# Hat_CoVASPSy_v1re2.net
KiCad netlist of a schematic drawn in EAGLE
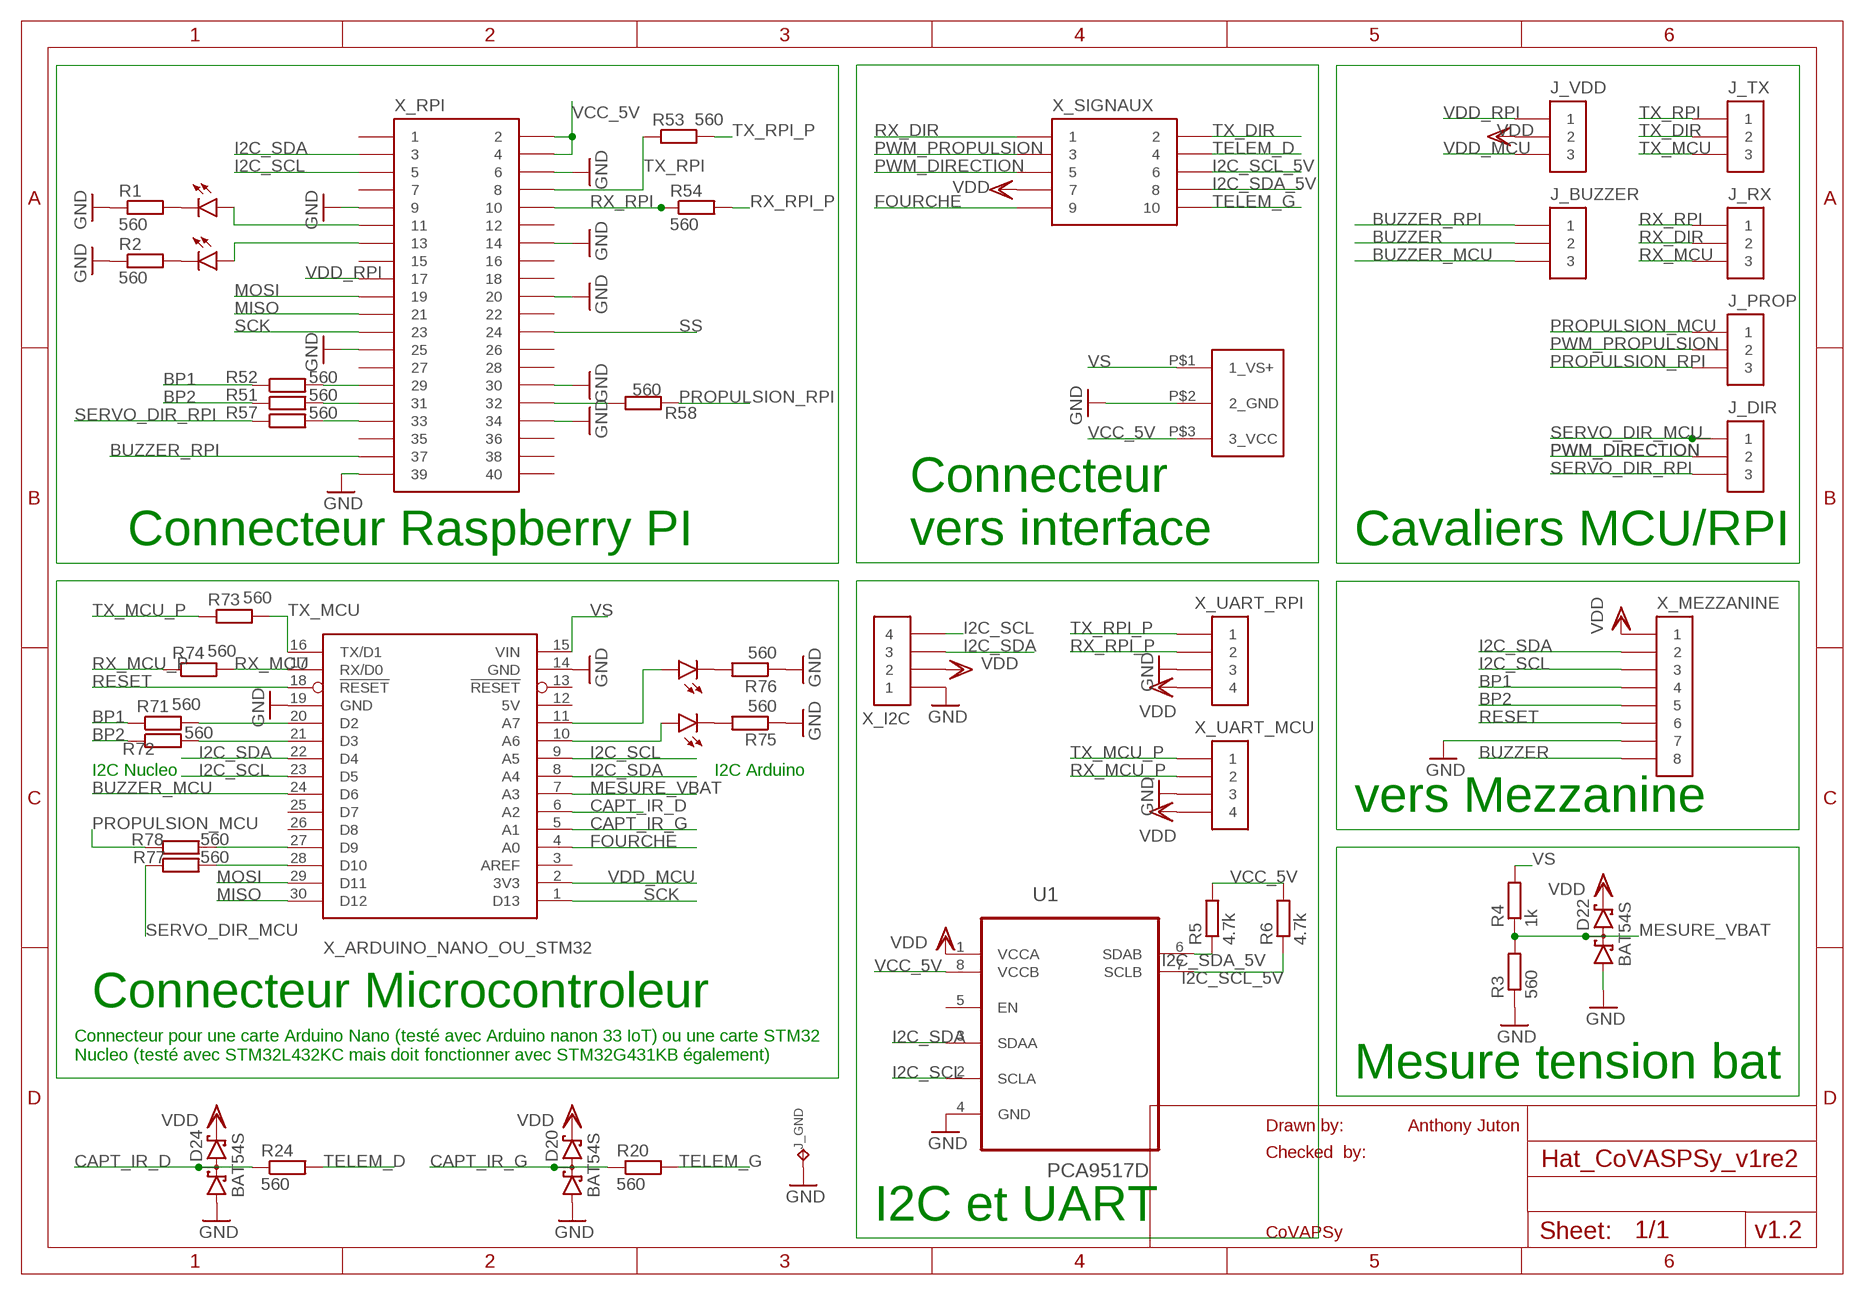
[diagram p0: schematic, sheet 1]

(export (version "E")
  (design (tool "Eeschema 10.0.6"))
  (components
    (comp (ref "D20")
      (value "BAT54S")
      (footprint "eagle-import:SOT23")
      (libsource (lib "eagle-import") (part "BAT54S"))
    )
    (comp (ref "D22")
      (value "BAT54S")
      (footprint "eagle-import:SOT23")
      (libsource (lib "eagle-import") (part "BAT54S"))
    )
    (comp (ref "D24")
      (value "BAT54S")
      (footprint "eagle-import:SOT23")
      (libsource (lib "eagle-import") (part "BAT54S"))
    )
    (comp (ref "J_BUZZER")
      (value "CAVALIER_3")
      (footprint "eagle-import:CAVALIER_3")
      (libsource (lib "eagle-import") (part "CAVALIER_3"))
    )
    (comp (ref "J_DIR")
      (value "CAVALIER_3")
      (footprint "eagle-import:CAVALIER_3")
      (libsource (lib "eagle-import") (part "CAVALIER_3"))
    )
    (comp (ref "J_GND")
      (value "COSSE_POIGN")
      (footprint "eagle-import:COSSE_POIGNARD")
      (libsource (lib "eagle-import") (part "COSSE_POIGN"))
    )
    (comp (ref "J_PROP")
      (value "CAVALIER_3")
      (footprint "eagle-import:CAVALIER_3")
      (libsource (lib "eagle-import") (part "CAVALIER_3"))
    )
    (comp (ref "J_RX")
      (value "CAVALIER_3")
      (footprint "eagle-import:CAVALIER_3")
      (libsource (lib "eagle-import") (part "CAVALIER_3"))
    )
    (comp (ref "J_TX")
      (value "CAVALIER_3")
      (footprint "eagle-import:CAVALIER_3")
      (libsource (lib "eagle-import") (part "CAVALIER_3"))
    )
    (comp (ref "J_VDD")
      (value "CAVALIER_3")
      (footprint "eagle-import:CAVALIER_3")
      (libsource (lib "eagle-import") (part "CAVALIER_3"))
    )
    (comp (ref "LED1")
      (value "LEDSML1206")
      (footprint "eagle-import:SML1206")
      (libsource (lib "eagle-import") (part "LEDSML1206"))
    )
    (comp (ref "LED2")
      (value "LEDSML1206")
      (footprint "eagle-import:SML1206")
      (libsource (lib "eagle-import") (part "LEDSML1206"))
    )
    (comp (ref "LED3")
      (value "LEDSML1206")
      (footprint "eagle-import:SML1206")
      (libsource (lib "eagle-import") (part "LEDSML1206"))
    )
    (comp (ref "LED4")
      (value "LEDSML1206")
      (footprint "eagle-import:SML1206")
      (libsource (lib "eagle-import") (part "LEDSML1206"))
    )
    (comp (ref "R1")
      (value "560")
      (footprint "eagle-import:M1206")
      (libsource (lib "eagle-import") (part "R-EU_M1206"))
    )
    (comp (ref "R2")
      (value "560")
      (footprint "eagle-import:M1206")
      (libsource (lib "eagle-import") (part "R-EU_M1206"))
    )
    (comp (ref "R3")
      (value "560")
      (footprint "eagle-import:M1206")
      (libsource (lib "eagle-import") (part "R-EU_M1206"))
    )
    (comp (ref "R4")
      (value "1k")
      (footprint "eagle-import:M1206")
      (libsource (lib "eagle-import") (part "R-EU_M1206"))
    )
    (comp (ref "R5")
      (value "4.7k")
      (footprint "eagle-import:M1206")
      (libsource (lib "eagle-import") (part "R-EU_M1206"))
    )
    (comp (ref "R6")
      (value "4.7k")
      (footprint "eagle-import:M1206")
      (libsource (lib "eagle-import") (part "R-EU_M1206"))
    )
    (comp (ref "R20")
      (value "560")
      (footprint "eagle-import:M1206")
      (libsource (lib "eagle-import") (part "R-EU_M1206"))
    )
    (comp (ref "R24")
      (value "560")
      (footprint "eagle-import:M1206")
      (libsource (lib "eagle-import") (part "R-EU_M1206"))
    )
    (comp (ref "R51")
      (value "560")
      (footprint "eagle-import:M1206")
      (libsource (lib "eagle-import") (part "R-EU_M1206"))
    )
    (comp (ref "R52")
      (value "560")
      (footprint "eagle-import:M1206")
      (libsource (lib "eagle-import") (part "R-EU_M1206"))
    )
    (comp (ref "R53")
      (value "560")
      (footprint "eagle-import:M1206")
      (libsource (lib "eagle-import") (part "R-EU_M1206"))
    )
    (comp (ref "R54")
      (value "560")
      (footprint "eagle-import:M1206")
      (libsource (lib "eagle-import") (part "R-EU_M1206"))
    )
    (comp (ref "R57")
      (value "560")
      (footprint "eagle-import:M1206")
      (libsource (lib "eagle-import") (part "R-EU_M1206"))
    )
    (comp (ref "R58")
      (value "560")
      (footprint "eagle-import:M1206")
      (libsource (lib "eagle-import") (part "R-EU_M1206"))
    )
    (comp (ref "R71")
      (value "560")
      (footprint "eagle-import:M1206")
      (libsource (lib "eagle-import") (part "R-EU_M1206"))
    )
    (comp (ref "R72")
      (value "560")
      (footprint "eagle-import:M1206")
      (libsource (lib "eagle-import") (part "R-EU_M1206"))
    )
    (comp (ref "R73")
      (value "560")
      (footprint "eagle-import:M1206")
      (libsource (lib "eagle-import") (part "R-EU_M1206"))
    )
    (comp (ref "R74")
      (value "560")
      (footprint "eagle-import:M1206")
      (libsource (lib "eagle-import") (part "R-EU_M1206"))
    )
    (comp (ref "R75")
      (value "560")
      (footprint "eagle-import:M1206")
      (libsource (lib "eagle-import") (part "R-EU_M1206"))
    )
    (comp (ref "R76")
      (value "560")
      (footprint "eagle-import:M1206")
      (libsource (lib "eagle-import") (part "R-EU_M1206"))
    )
    (comp (ref "R77")
      (value "560")
      (footprint "eagle-import:M1206")
      (libsource (lib "eagle-import") (part "R-EU_M1206"))
    )
    (comp (ref "R78")
      (value "560")
      (footprint "eagle-import:M1206")
      (libsource (lib "eagle-import") (part "R-EU_M1206"))
    )
    (comp (ref "U1")
      (value "PCA9517D")
      (footprint "eagle-import:SOIC127P600X175-8N")
      (libsource (lib "eagle-import") (part "PCA9517D"))
    )
    (comp (ref "X_ALIM")
      (value "CONN_ALIM_3TROUS")
      (footprint "eagle-import:CONN_ALIM_3TROUS")
      (libsource (lib "eagle-import") (part "CONN_ALIM_3TROUS"))
    )
    (comp (ref "X_ARDUINO_NANO_OU_STM32")
      (value "ARDUINO_NANO_STM32_NUCLEO")
      (footprint "eagle-import:ARDUINO_NANO_STM32_NUCLEO")
      (libsource (lib "eagle-import") (part "ARDUINO_NANO_STM32_NUCLEO"))
    )
    (comp (ref "X_I2C")
      (value "MOLEX_4_DROIT")
      (footprint "eagle-import:MOLEX_4_DROIT")
      (libsource (lib "eagle-import") (part "MOLEX_4_DROIT"))
    )
    (comp (ref "X_MEZZANINE")
      (value "MOLEX_8_DROIT")
      (footprint "eagle-import:MOLEX_8_DROIT")
      (libsource (lib "eagle-import") (part "MOLEX_8_DROIT"))
    )
    (comp (ref "X_RPI")
      (value "HEADER_20X2")
      (footprint "eagle-import:HEADER_20X2")
      (libsource (lib "eagle-import") (part "HEADER_20X2"))
    )
    (comp (ref "X_SIGNAUX")
      (value "HEADER_5X2")
      (footprint "eagle-import:HEADER_5X2")
      (libsource (lib "eagle-import") (part "HEADER_5X2"))
    )
    (comp (ref "X_UART_MCU")
      (value "MOLEX_4_DROIT")
      (footprint "eagle-import:MOLEX_4_DROIT")
      (libsource (lib "eagle-import") (part "MOLEX_4_DROIT"))
    )
    (comp (ref "X_UART_RPI")
      (value "MOLEX_4_DROIT")
      (footprint "eagle-import:MOLEX_4_DROIT")
      (libsource (lib "eagle-import") (part "MOLEX_4_DROIT"))
    )
  )
  (nets
    (net (code "1") (name "/5V") (class "Default")
      (node (ref "X_ARDUINO_NANO_OU_STM32") (pin "12") (pinfunction "5V_12") (pintype "power_in"))
    )
    (net (code "2") (name "/BP1") (class "Default")
      (node (ref "R52") (pin "1") (pinfunction "1_1") (pintype "passive"))
      (node (ref "R71") (pin "1") (pinfunction "1_1") (pintype "passive"))
      (node (ref "X_MEZZANINE") (pin "P$4") (pinfunction "4_P$4") (pintype "bidirectional"))
    )
    (net (code "3") (name "/BP2") (class "Default")
      (node (ref "R51") (pin "1") (pinfunction "1_1") (pintype "passive"))
      (node (ref "R72") (pin "1") (pinfunction "1_1") (pintype "passive"))
      (node (ref "X_MEZZANINE") (pin "P$5") (pinfunction "5_P$5") (pintype "bidirectional"))
    )
    (net (code "4") (name "/BUZZER") (class "Default")
      (node (ref "J_BUZZER") (pin "P$2") (pinfunction "2_P$2") (pintype "bidirectional"))
      (node (ref "X_MEZZANINE") (pin "P$8") (pinfunction "8_P$8") (pintype "bidirectional"))
    )
    (net (code "5") (name "/BUZZER_MCU") (class "Default")
      (node (ref "J_BUZZER") (pin "P$3") (pinfunction "3_P$3") (pintype "bidirectional"))
      (node (ref "X_ARDUINO_NANO_OU_STM32") (pin "24") (pinfunction "D6_24") (pintype "bidirectional"))
    )
    (net (code "6") (name "/BUZZER_RPI") (class "Default")
      (node (ref "J_BUZZER") (pin "P$1") (pinfunction "1_P$1") (pintype "bidirectional"))
      (node (ref "X_RPI") (pin "P$37") (pinfunction "37_P$37") (pintype "bidirectional"))
    )
    (net (code "7") (name "/CAPT_IR_D") (class "Default")
      (node (ref "D24") (pin "3") (pinfunction "C1A2_3") (pintype "passive"))
      (node (ref "R24") (pin "1") (pinfunction "1_1") (pintype "passive"))
      (node (ref "X_ARDUINO_NANO_OU_STM32") (pin "6") (pinfunction "A2_6") (pintype "bidirectional"))
    )
    (net (code "8") (name "/CAPT_IR_G") (class "Default")
      (node (ref "D20") (pin "3") (pinfunction "C1A2_3") (pintype "passive"))
      (node (ref "R20") (pin "1") (pinfunction "1_1") (pintype "passive"))
      (node (ref "X_ARDUINO_NANO_OU_STM32") (pin "5") (pinfunction "A1_5") (pintype "bidirectional"))
    )
    (net (code "9") (name "/FOURCHE") (class "Default")
      (node (ref "X_ARDUINO_NANO_OU_STM32") (pin "4") (pinfunction "A0_4") (pintype "bidirectional"))
      (node (ref "X_SIGNAUX") (pin "P$9") (pinfunction "9_P$9") (pintype "bidirectional"))
    )
    (net (code "10") (name "/I2C_SCL") (class "Default")
      (node (ref "U1") (pin "2") (pinfunction "SCLA_2") (pintype "input"))
      (node (ref "X_ARDUINO_NANO_OU_STM32") (pin "23") (pinfunction "D5_23") (pintype "bidirectional"))
      (node (ref "X_ARDUINO_NANO_OU_STM32") (pin "9") (pinfunction "A5_9") (pintype "bidirectional"))
      (node (ref "X_I2C") (pin "P$4") (pinfunction "4_P$4") (pintype "bidirectional"))
      (node (ref "X_MEZZANINE") (pin "P$3") (pinfunction "3_P$3") (pintype "bidirectional"))
      (node (ref "X_RPI") (pin "P$5") (pinfunction "5_P$5") (pintype "bidirectional"))
    )
    (net (code "11") (name "/I2C_SCL_5V") (class "Default")
      (node (ref "R6") (pin "1") (pinfunction "1_1") (pintype "passive"))
      (node (ref "U1") (pin "7") (pinfunction "SCLB_7") (pintype "output"))
      (node (ref "X_SIGNAUX") (pin "P$6") (pinfunction "6_P$6") (pintype "bidirectional"))
    )
    (net (code "12") (name "/I2C_SDA") (class "Default")
      (node (ref "U1") (pin "3") (pinfunction "SDAA_3") (pintype "input"))
      (node (ref "X_ARDUINO_NANO_OU_STM32") (pin "22") (pinfunction "D4_22") (pintype "bidirectional"))
      (node (ref "X_ARDUINO_NANO_OU_STM32") (pin "8") (pinfunction "A4_8") (pintype "bidirectional"))
      (node (ref "X_I2C") (pin "P$3") (pinfunction "3_P$3") (pintype "bidirectional"))
      (node (ref "X_MEZZANINE") (pin "P$2") (pinfunction "2_P$2") (pintype "bidirectional"))
      (node (ref "X_RPI") (pin "P$3") (pinfunction "3_P$3") (pintype "bidirectional"))
    )
    (net (code "13") (name "/I2C_SDA_5V") (class "Default")
      (node (ref "R5") (pin "1") (pinfunction "1_1") (pintype "passive"))
      (node (ref "U1") (pin "6") (pinfunction "SDAB_6") (pintype "output"))
      (node (ref "X_SIGNAUX") (pin "P$8") (pinfunction "8_P$8") (pintype "bidirectional"))
    )
    (net (code "14") (name "/MESURE_VBAT") (class "Default")
      (node (ref "D22") (pin "3") (pinfunction "C1A2_3") (pintype "passive"))
      (node (ref "R3") (pin "2") (pinfunction "2_2") (pintype "passive"))
      (node (ref "R4") (pin "1") (pinfunction "1_1") (pintype "passive"))
      (node (ref "X_ARDUINO_NANO_OU_STM32") (pin "7") (pinfunction "A3_7") (pintype "bidirectional"))
    )
    (net (code "15") (name "/MISO") (class "Default")
      (node (ref "X_ARDUINO_NANO_OU_STM32") (pin "30") (pinfunction "D12_30") (pintype "bidirectional"))
      (node (ref "X_RPI") (pin "P$21") (pinfunction "21_P$21") (pintype "bidirectional"))
    )
    (net (code "16") (name "/MOSI") (class "Default")
      (node (ref "X_ARDUINO_NANO_OU_STM32") (pin "29") (pinfunction "D11_29") (pintype "bidirectional"))
      (node (ref "X_RPI") (pin "P$19") (pinfunction "19_P$19") (pintype "bidirectional"))
    )
    (net (code "20") (name "/PROPULSION_MCU") (class "Default")
      (node (ref "J_PROP") (pin "P$1") (pinfunction "1_P$1") (pintype "bidirectional"))
      (node (ref "R78") (pin "1") (pinfunction "1_1") (pintype "passive"))
    )
    (net (code "21") (name "/PROPULSION_RPI") (class "Default")
      (node (ref "J_PROP") (pin "P$3") (pinfunction "3_P$3") (pintype "bidirectional"))
      (node (ref "R58") (pin "2") (pinfunction "2_2") (pintype "passive"))
    )
    (net (code "22") (name "/PWM_DIRECTION") (class "Default")
      (node (ref "J_DIR") (pin "P$2") (pinfunction "2_P$2") (pintype "bidirectional"))
      (node (ref "X_SIGNAUX") (pin "P$5") (pinfunction "5_P$5") (pintype "bidirectional"))
    )
    (net (code "23") (name "/PWM_PROPULSION") (class "Default")
      (node (ref "J_PROP") (pin "P$2") (pinfunction "2_P$2") (pintype "bidirectional"))
      (node (ref "X_SIGNAUX") (pin "P$3") (pinfunction "3_P$3") (pintype "bidirectional"))
    )
    (net (code "24") (name "/RESET") (class "Default")
      (node (ref "X_ARDUINO_NANO_OU_STM32") (pin "18") (pinfunction "~{RESET}_18") (pintype "input"))
      (node (ref "X_MEZZANINE") (pin "P$6") (pinfunction "6_P$6") (pintype "bidirectional"))
    )
    (net (code "25") (name "/RX_DIR") (class "Default")
      (node (ref "J_RX") (pin "P$2") (pinfunction "2_P$2") (pintype "bidirectional"))
      (node (ref "X_SIGNAUX") (pin "P$1") (pinfunction "1_P$1") (pintype "bidirectional"))
    )
    (net (code "26") (name "/RX_MCU") (class "Default")
      (node (ref "J_RX") (pin "P$3") (pinfunction "3_P$3") (pintype "bidirectional"))
      (node (ref "R74") (pin "2") (pinfunction "2_2") (pintype "passive"))
      (node (ref "X_ARDUINO_NANO_OU_STM32") (pin "17") (pinfunction "RX/D0_17") (pintype "bidirectional"))
    )
    (net (code "27") (name "/RX_MCU_P") (class "Default")
      (node (ref "R74") (pin "1") (pinfunction "1_1") (pintype "passive"))
      (node (ref "X_UART_MCU") (pin "P$2") (pinfunction "2_P$2") (pintype "bidirectional"))
    )
    (net (code "28") (name "/RX_RPI") (class "Default")
      (node (ref "J_RX") (pin "P$1") (pinfunction "1_P$1") (pintype "bidirectional"))
      (node (ref "R54") (pin "1") (pinfunction "1_1") (pintype "passive"))
      (node (ref "X_RPI") (pin "P$10") (pinfunction "10_P$10") (pintype "bidirectional"))
    )
    (net (code "29") (name "/RX_RPI_P") (class "Default")
      (node (ref "R54") (pin "2") (pinfunction "2_2") (pintype "passive"))
      (node (ref "X_UART_RPI") (pin "P$2") (pinfunction "2_P$2") (pintype "bidirectional"))
    )
    (net (code "30") (name "/SCK") (class "Default")
      (node (ref "X_ARDUINO_NANO_OU_STM32") (pin "1") (pinfunction "D13_1") (pintype "bidirectional"))
      (node (ref "X_RPI") (pin "P$23") (pinfunction "23_P$23") (pintype "bidirectional"))
    )
    (net (code "31") (name "/SERVO_DIR_MCU") (class "Default")
      (node (ref "J_DIR") (pin "P$1") (pinfunction "1_P$1") (pintype "bidirectional"))
      (node (ref "R77") (pin "1") (pinfunction "1_1") (pintype "passive"))
    )
    (net (code "32") (name "/SERVO_DIR_RPI") (class "Default")
      (node (ref "J_DIR") (pin "P$3") (pinfunction "3_P$3") (pintype "bidirectional"))
      (node (ref "R57") (pin "1") (pinfunction "1_1") (pintype "passive"))
    )
    (net (code "33") (name "/SS") (class "Default")
      (node (ref "X_RPI") (pin "P$24") (pinfunction "24_P$24") (pintype "bidirectional"))
    )
    (net (code "34") (name "/TELEM_D") (class "Default")
      (node (ref "R24") (pin "2") (pinfunction "2_2") (pintype "passive"))
      (node (ref "X_SIGNAUX") (pin "P$4") (pinfunction "4_P$4") (pintype "bidirectional"))
    )
    (net (code "35") (name "/TELEM_G") (class "Default")
      (node (ref "R20") (pin "2") (pinfunction "2_2") (pintype "passive"))
      (node (ref "X_SIGNAUX") (pin "P$10") (pinfunction "10_P$10") (pintype "bidirectional"))
    )
    (net (code "36") (name "/TX_DIR") (class "Default")
      (node (ref "J_TX") (pin "P$2") (pinfunction "2_P$2") (pintype "bidirectional"))
      (node (ref "X_SIGNAUX") (pin "P$2") (pinfunction "2_P$2") (pintype "bidirectional"))
    )
    (net (code "37") (name "/TX_MCU") (class "Default")
      (node (ref "J_TX") (pin "P$3") (pinfunction "3_P$3") (pintype "bidirectional"))
      (node (ref "R73") (pin "2") (pinfunction "2_2") (pintype "passive"))
      (node (ref "X_ARDUINO_NANO_OU_STM32") (pin "16") (pinfunction "TX/D1_16") (pintype "bidirectional"))
    )
    (net (code "38") (name "/TX_MCU_P") (class "Default")
      (node (ref "R73") (pin "1") (pinfunction "1_1") (pintype "passive"))
      (node (ref "X_UART_MCU") (pin "P$1") (pinfunction "1_P$1") (pintype "bidirectional"))
    )
    (net (code "39") (name "/TX_RPI") (class "Default")
      (node (ref "J_TX") (pin "P$1") (pinfunction "1_P$1") (pintype "bidirectional"))
      (node (ref "R53") (pin "1") (pinfunction "1_1") (pintype "passive"))
      (node (ref "X_RPI") (pin "P$8") (pinfunction "8_P$8") (pintype "bidirectional"))
    )
    (net (code "40") (name "/TX_RPI_P") (class "Default")
      (node (ref "R53") (pin "2") (pinfunction "2_2") (pintype "passive"))
      (node (ref "X_UART_RPI") (pin "P$1") (pinfunction "1_P$1") (pintype "bidirectional"))
    )
    (net (code "41") (name "/VCC_5V") (class "Default")
      (node (ref "R5") (pin "2") (pinfunction "2_2") (pintype "passive"))
      (node (ref "R6") (pin "2") (pinfunction "2_2") (pintype "passive"))
      (node (ref "U1") (pin "8") (pinfunction "VCCB_8") (pintype "power_in"))
      (node (ref "X_ALIM") (pin "P$3") (pinfunction "3_VCC_P$3") (pintype "bidirectional"))
      (node (ref "X_RPI") (pin "P$2") (pinfunction "2_P$2") (pintype "bidirectional"))
      (node (ref "X_RPI") (pin "P$4") (pinfunction "4_P$4") (pintype "bidirectional"))
    )
    (net (code "42") (name "/VDD_MCU") (class "Default")
      (node (ref "J_VDD") (pin "P$3") (pinfunction "3_P$3") (pintype "bidirectional"))
      (node (ref "X_ARDUINO_NANO_OU_STM32") (pin "2") (pinfunction "3V3_2") (pintype "output"))
    )
    (net (code "43") (name "/VDD_RPI") (class "Default")
      (node (ref "J_VDD") (pin "P$1") (pinfunction "1_P$1") (pintype "bidirectional"))
      (node (ref "X_RPI") (pin "P$17") (pinfunction "17_P$17") (pintype "bidirectional"))
    )
    (net (code "44") (name "/VS") (class "Default")
      (node (ref "R4") (pin "2") (pinfunction "2_2") (pintype "passive"))
      (node (ref "X_ALIM") (pin "P$1") (pinfunction "1_VS+_P$1") (pintype "bidirectional"))
      (node (ref "X_ARDUINO_NANO_OU_STM32") (pin "15") (pinfunction "VIN_15") (pintype "power_in"))
    )
    (net (code "45") (name "GND") (class "Default")
      (node (ref "D20") (pin "1") (pinfunction "A1_1") (pintype "passive"))
      (node (ref "D22") (pin "1") (pinfunction "A1_1") (pintype "passive"))
      (node (ref "D24") (pin "1") (pinfunction "A1_1") (pintype "passive"))
      (node (ref "J_GND") (pin "P$1") (pinfunction "P$1_P$1") (pintype "bidirectional"))
      (node (ref "R1") (pin "1") (pinfunction "1_1") (pintype "passive"))
      (node (ref "R2") (pin "1") (pinfunction "1_1") (pintype "passive"))
      (node (ref "R3") (pin "1") (pinfunction "1_1") (pintype "passive"))
      (node (ref "R75") (pin "1") (pinfunction "1_1") (pintype "passive"))
      (node (ref "R76") (pin "1") (pinfunction "1_1") (pintype "passive"))
      (node (ref "U1") (pin "4") (pinfunction "GND_4") (pintype "passive"))
      (node (ref "X_ALIM") (pin "P$2") (pinfunction "2_GND_P$2") (pintype "bidirectional"))
      (node (ref "X_ARDUINO_NANO_OU_STM32") (pin "14") (pinfunction "GND_14") (pintype "power_in"))
      (node (ref "X_ARDUINO_NANO_OU_STM32") (pin "19") (pinfunction "GND_19") (pintype "power_in"))
      (node (ref "X_I2C") (pin "P$1") (pinfunction "1_P$1") (pintype "bidirectional"))
      (node (ref "X_MEZZANINE") (pin "P$7") (pinfunction "7_P$7") (pintype "bidirectional"))
      (node (ref "X_RPI") (pin "P$14") (pinfunction "14_P$14") (pintype "bidirectional"))
      (node (ref "X_RPI") (pin "P$20") (pinfunction "20_P$20") (pintype "bidirectional"))
      (node (ref "X_RPI") (pin "P$25") (pinfunction "25_P$25") (pintype "bidirectional"))
      (node (ref "X_RPI") (pin "P$30") (pinfunction "30_P$30") (pintype "bidirectional"))
      (node (ref "X_RPI") (pin "P$34") (pinfunction "34_P$34") (pintype "bidirectional"))
      (node (ref "X_RPI") (pin "P$39") (pinfunction "39_P$39") (pintype "bidirectional"))
      (node (ref "X_RPI") (pin "P$6") (pinfunction "6_P$6") (pintype "bidirectional"))
      (node (ref "X_RPI") (pin "P$9") (pinfunction "9_P$9") (pintype "bidirectional"))
      (node (ref "X_UART_MCU") (pin "P$3") (pinfunction "3_P$3") (pintype "bidirectional"))
      (node (ref "X_UART_RPI") (pin "P$3") (pinfunction "3_P$3") (pintype "bidirectional"))
    )
    (net (code "46") (name "Net-(LED1-PadC)") (class "Default")
      (node (ref "LED1") (pin "C") (pinfunction "C_C") (pintype "passive"))
      (node (ref "R1") (pin "2") (pinfunction "2_2") (pintype "passive"))
    )
    (net (code "47") (name "Net-(LED2-PadC)") (class "Default")
      (node (ref "LED2") (pin "C") (pinfunction "C_C") (pintype "passive"))
      (node (ref "R2") (pin "2") (pinfunction "2_2") (pintype "passive"))
    )
    (net (code "48") (name "Net-(LED3-PadC)") (class "Default")
      (node (ref "LED3") (pin "C") (pinfunction "C_C") (pintype "passive"))
      (node (ref "R76") (pin "2") (pinfunction "2_2") (pintype "passive"))
    )
    (net (code "49") (name "Net-(LED4-PadC)") (class "Default")
      (node (ref "LED4") (pin "C") (pinfunction "C_C") (pintype "passive"))
      (node (ref "R75") (pin "2") (pinfunction "2_2") (pintype "passive"))
    )
    (net (code "50") (name "Net-(X_ARDUINO_NANO_OU_STM32-A6)") (class "Default")
      (node (ref "LED4") (pin "A") (pinfunction "A_A") (pintype "passive"))
      (node (ref "X_ARDUINO_NANO_OU_STM32") (pin "10") (pinfunction "A6_10") (pintype "bidirectional"))
    )
    (net (code "51") (name "Net-(X_ARDUINO_NANO_OU_STM32-A7)") (class "Default")
      (node (ref "LED3") (pin "A") (pinfunction "A_A") (pintype "passive"))
      (node (ref "X_ARDUINO_NANO_OU_STM32") (pin "11") (pinfunction "A7_11") (pintype "bidirectional"))
    )
    (net (code "52") (name "Net-(X_ARDUINO_NANO_OU_STM32-D2)") (class "Default")
      (node (ref "R71") (pin "2") (pinfunction "2_2") (pintype "passive"))
      (node (ref "X_ARDUINO_NANO_OU_STM32") (pin "20") (pinfunction "D2_20") (pintype "bidirectional"))
    )
    (net (code "53") (name "Net-(X_ARDUINO_NANO_OU_STM32-D3)") (class "Default")
      (node (ref "R72") (pin "2") (pinfunction "2_2") (pintype "passive"))
      (node (ref "X_ARDUINO_NANO_OU_STM32") (pin "21") (pinfunction "D3_21") (pintype "bidirectional"))
    )
    (net (code "54") (name "Net-(X_ARDUINO_NANO_OU_STM32-D9)") (class "Default")
      (node (ref "R78") (pin "2") (pinfunction "2_2") (pintype "passive"))
      (node (ref "X_ARDUINO_NANO_OU_STM32") (pin "27") (pinfunction "D9_27") (pintype "bidirectional"))
    )
    (net (code "55") (name "Net-(X_ARDUINO_NANO_OU_STM32-D10)") (class "Default")
      (node (ref "R77") (pin "2") (pinfunction "2_2") (pintype "passive"))
      (node (ref "X_ARDUINO_NANO_OU_STM32") (pin "28") (pinfunction "D10_28") (pintype "bidirectional"))
    )
    (net (code "56") (name "Net-(X_RPI-11)") (class "Default")
      (node (ref "LED1") (pin "A") (pinfunction "A_A") (pintype "passive"))
      (node (ref "X_RPI") (pin "P$11") (pinfunction "11_P$11") (pintype "bidirectional"))
    )
    (net (code "57") (name "Net-(X_RPI-13)") (class "Default")
      (node (ref "LED2") (pin "A") (pinfunction "A_A") (pintype "passive"))
      (node (ref "X_RPI") (pin "P$13") (pinfunction "13_P$13") (pintype "bidirectional"))
    )
    (net (code "58") (name "Net-(X_RPI-29)") (class "Default")
      (node (ref "R52") (pin "2") (pinfunction "2_2") (pintype "passive"))
      (node (ref "X_RPI") (pin "P$29") (pinfunction "29_P$29") (pintype "bidirectional"))
    )
    (net (code "59") (name "Net-(X_RPI-31)") (class "Default")
      (node (ref "R51") (pin "2") (pinfunction "2_2") (pintype "passive"))
      (node (ref "X_RPI") (pin "P$31") (pinfunction "31_P$31") (pintype "bidirectional"))
    )
    (net (code "60") (name "Net-(X_RPI-32)") (class "Default")
      (node (ref "R58") (pin "1") (pinfunction "1_1") (pintype "passive"))
      (node (ref "X_RPI") (pin "P$32") (pinfunction "32_P$32") (pintype "bidirectional"))
    )
    (net (code "61") (name "Net-(X_RPI-33)") (class "Default")
      (node (ref "R57") (pin "2") (pinfunction "2_2") (pintype "passive"))
      (node (ref "X_RPI") (pin "P$33") (pinfunction "33_P$33") (pintype "bidirectional"))
    )
    (net (code "62") (name "VDD") (class "Default")
      (node (ref "D20") (pin "2") (pinfunction "C2_2") (pintype "passive"))
      (node (ref "D22") (pin "2") (pinfunction "C2_2") (pintype "passive"))
      (node (ref "D24") (pin "2") (pinfunction "C2_2") (pintype "passive"))
      (node (ref "J_VDD") (pin "P$2") (pinfunction "2_P$2") (pintype "bidirectional"))
      (node (ref "U1") (pin "1") (pinfunction "VCCA_1") (pintype "power_in"))
      (node (ref "X_I2C") (pin "P$2") (pinfunction "2_P$2") (pintype "bidirectional"))
      (node (ref "X_MEZZANINE") (pin "P$1") (pinfunction "1_P$1") (pintype "bidirectional"))
      (node (ref "X_SIGNAUX") (pin "P$7") (pinfunction "7_P$7") (pintype "bidirectional"))
      (node (ref "X_UART_MCU") (pin "P$4") (pinfunction "4_P$4") (pintype "bidirectional"))
      (node (ref "X_UART_RPI") (pin "P$4") (pinfunction "4_P$4") (pintype "bidirectional"))
    )
    (net (code "63") (name "unconnected-(U1-EN-Pad5)") (class "Default")
      (node (ref "U1") (pin "5") (pinfunction "EN_5") (pintype "input"))
    )
    (net (code "64") (name "unconnected-(X_ARDUINO_NANO_OU_STM32-AREF-Pad3)") (class "Default")
      (node (ref "X_ARDUINO_NANO_OU_STM32") (pin "3") (pinfunction "AREF_3") (pintype "input"))
    )
    (net (code "65") (name "unconnected-(X_ARDUINO_NANO_OU_STM32-D7-Pad25)") (class "Default")
      (node (ref "X_ARDUINO_NANO_OU_STM32") (pin "25") (pinfunction "D7_25") (pintype "bidirectional"))
    )
    (net (code "66") (name "unconnected-(X_ARDUINO_NANO_OU_STM32-D8-Pad26)") (class "Default")
      (node (ref "X_ARDUINO_NANO_OU_STM32") (pin "26") (pinfunction "D8_26") (pintype "bidirectional"))
    )
    (net (code "67") (name "unconnected-(X_ARDUINO_NANO_OU_STM32-~{RESET}-Pad13)") (class "Default")
      (node (ref "X_ARDUINO_NANO_OU_STM32") (pin "13") (pinfunction "~{RESET}_13") (pintype "input"))
    )
    (net (code "68") (name "unconnected-(X_RPI-1-PadP$1)") (class "Default")
      (node (ref "X_RPI") (pin "P$1") (pinfunction "1_P$1") (pintype "bidirectional"))
    )
    (net (code "69") (name "unconnected-(X_RPI-7-PadP$7)") (class "Default")
      (node (ref "X_RPI") (pin "P$7") (pinfunction "7_P$7") (pintype "bidirectional"))
    )
    (net (code "70") (name "unconnected-(X_RPI-12-PadP$12)") (class "Default")
      (node (ref "X_RPI") (pin "P$12") (pinfunction "12_P$12") (pintype "bidirectional"))
    )
    (net (code "71") (name "unconnected-(X_RPI-15-PadP$15)") (class "Default")
      (node (ref "X_RPI") (pin "P$15") (pinfunction "15_P$15") (pintype "bidirectional"))
    )
    (net (code "72") (name "unconnected-(X_RPI-16-PadP$16)") (class "Default")
      (node (ref "X_RPI") (pin "P$16") (pinfunction "16_P$16") (pintype "bidirectional"))
    )
    (net (code "73") (name "unconnected-(X_RPI-18-PadP$18)") (class "Default")
      (node (ref "X_RPI") (pin "P$18") (pinfunction "18_P$18") (pintype "bidirectional"))
    )
    (net (code "74") (name "unconnected-(X_RPI-22-PadP$22)") (class "Default")
      (node (ref "X_RPI") (pin "P$22") (pinfunction "22_P$22") (pintype "bidirectional"))
    )
    (net (code "75") (name "unconnected-(X_RPI-26-PadP$26)") (class "Default")
      (node (ref "X_RPI") (pin "P$26") (pinfunction "26_P$26") (pintype "bidirectional"))
    )
    (net (code "76") (name "unconnected-(X_RPI-27-PadP$27)") (class "Default")
      (node (ref "X_RPI") (pin "P$27") (pinfunction "27_P$27") (pintype "bidirectional"))
    )
    (net (code "77") (name "unconnected-(X_RPI-28-PadP$28)") (class "Default")
      (node (ref "X_RPI") (pin "P$28") (pinfunction "28_P$28") (pintype "bidirectional"))
    )
    (net (code "78") (name "unconnected-(X_RPI-35-PadP$35)") (class "Default")
      (node (ref "X_RPI") (pin "P$35") (pinfunction "35_P$35") (pintype "bidirectional"))
    )
    (net (code "79") (name "unconnected-(X_RPI-36-PadP$36)") (class "Default")
      (node (ref "X_RPI") (pin "P$36") (pinfunction "36_P$36") (pintype "bidirectional"))
    )
    (net (code "80") (name "unconnected-(X_RPI-38-PadP$38)") (class "Default")
      (node (ref "X_RPI") (pin "P$38") (pinfunction "38_P$38") (pintype "bidirectional"))
    )
    (net (code "81") (name "unconnected-(X_RPI-40-PadP$40)") (class "Default")
      (node (ref "X_RPI") (pin "P$40") (pinfunction "40_P$40") (pintype "bidirectional"))
    )
  )
)
